# 32-16_adapter2.net
KiCad netlist of a schematic drawn in EAGLE
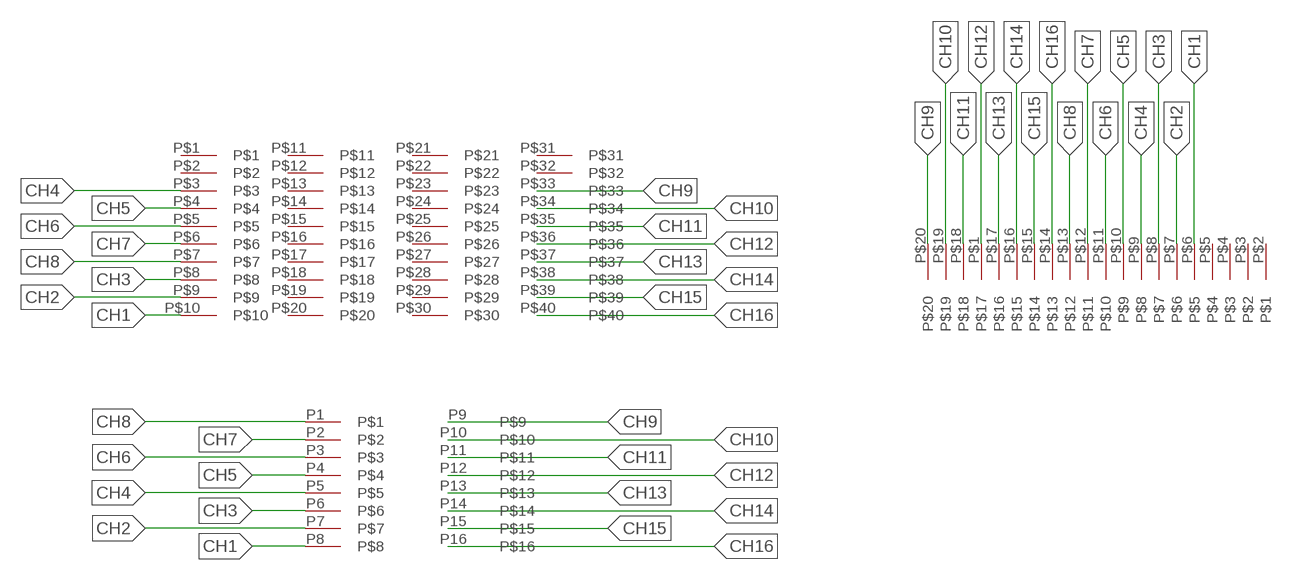
[diagram p0: schematic, sheet 1]

(export (version "E")
  (design (tool "Eeschema 10.0.6"))
  (components
    (comp (ref "U$1")
      (value "16_PAD")
      (footprint "eagle-import:16_PAD")
      (libsource (lib "eagle-import") (part "16_PAD"))
    )
    (comp (ref "U$2")
      (value "DIL-16CHN")
      (footprint "eagle-import:DIL-16CHN")
      (libsource (lib "eagle-import") (part "DIL-16CHN"))
    )
    (comp (ref "U$3")
      (value "MOLC-SAMTEC-32")
      (footprint "eagle-import:MOLC-SAMTEC-32")
      (libsource (lib "eagle-import") (part "MOLC-SAMTEC-32"))
    )
  )
  (nets
    (net (code "1") (name "CH1") (class "Default")
      (node (ref "U$1") (pin "P$6") (pinfunction "P$5_P$6") (pintype "bidirectional"))
      (node (ref "U$2") (pin "P8") (pinfunction "P$8_P8") (pintype "bidirectional"))
      (node (ref "U$3") (pin "P$10") (pinfunction "P$10_P$10") (pintype "bidirectional"))
    )
    (net (code "2") (name "CH2") (class "Default")
      (node (ref "U$1") (pin "P$7") (pinfunction "P$6_P$7") (pintype "bidirectional"))
      (node (ref "U$2") (pin "P7") (pinfunction "P$7_P7") (pintype "bidirectional"))
      (node (ref "U$3") (pin "P$9") (pinfunction "P$9_P$9") (pintype "bidirectional"))
    )
    (net (code "3") (name "CH3") (class "Default")
      (node (ref "U$1") (pin "P$8") (pinfunction "P$7_P$8") (pintype "bidirectional"))
      (node (ref "U$2") (pin "P6") (pinfunction "P$6_P6") (pintype "bidirectional"))
      (node (ref "U$3") (pin "P$8") (pinfunction "P$8_P$8") (pintype "bidirectional"))
    )
    (net (code "4") (name "CH4") (class "Default")
      (node (ref "U$1") (pin "P$9") (pinfunction "P$8_P$9") (pintype "bidirectional"))
      (node (ref "U$2") (pin "P5") (pinfunction "P$5_P5") (pintype "bidirectional"))
      (node (ref "U$3") (pin "P$3") (pinfunction "P$3_P$3") (pintype "bidirectional"))
    )
    (net (code "5") (name "CH5") (class "Default")
      (node (ref "U$1") (pin "P$10") (pinfunction "P$9_P$10") (pintype "bidirectional"))
      (node (ref "U$2") (pin "P4") (pinfunction "P$4_P4") (pintype "bidirectional"))
      (node (ref "U$3") (pin "P$4") (pinfunction "P$4_P$4") (pintype "bidirectional"))
    )
    (net (code "6") (name "CH6") (class "Default")
      (node (ref "U$1") (pin "P$11") (pinfunction "P$10_P$11") (pintype "bidirectional"))
      (node (ref "U$2") (pin "P3") (pinfunction "P$3_P3") (pintype "bidirectional"))
      (node (ref "U$3") (pin "P$5") (pinfunction "P$5_P$5") (pintype "bidirectional"))
    )
    (net (code "7") (name "CH7") (class "Default")
      (node (ref "U$1") (pin "P$12") (pinfunction "P$11_P$12") (pintype "bidirectional"))
      (node (ref "U$2") (pin "P2") (pinfunction "P$2_P2") (pintype "bidirectional"))
      (node (ref "U$3") (pin "P$6") (pinfunction "P$6_P$6") (pintype "bidirectional"))
    )
    (net (code "8") (name "CH8") (class "Default")
      (node (ref "U$1") (pin "P$13") (pinfunction "P$12_P$13") (pintype "bidirectional"))
      (node (ref "U$2") (pin "P1") (pinfunction "P$1_P1") (pintype "bidirectional"))
      (node (ref "U$3") (pin "P$7") (pinfunction "P$7_P$7") (pintype "bidirectional"))
    )
    (net (code "9") (name "CH9") (class "Default")
      (node (ref "U$1") (pin "P$20") (pinfunction "P$20_P$20") (pintype "bidirectional"))
      (node (ref "U$2") (pin "P9") (pinfunction "P$9_P9") (pintype "bidirectional"))
      (node (ref "U$3") (pin "P$33") (pinfunction "P$33_P$33") (pintype "bidirectional"))
    )
    (net (code "10") (name "CH10") (class "Default")
      (node (ref "U$1") (pin "P$19") (pinfunction "P$19_P$19") (pintype "bidirectional"))
      (node (ref "U$2") (pin "P10") (pinfunction "P$10_P10") (pintype "bidirectional"))
      (node (ref "U$3") (pin "P$34") (pinfunction "P$34_P$34") (pintype "bidirectional"))
    )
    (net (code "11") (name "CH11") (class "Default")
      (node (ref "U$1") (pin "P$18") (pinfunction "P$18_P$18") (pintype "bidirectional"))
      (node (ref "U$2") (pin "P11") (pinfunction "P$11_P11") (pintype "bidirectional"))
      (node (ref "U$3") (pin "P$35") (pinfunction "P$35_P$35") (pintype "bidirectional"))
    )
    (net (code "12") (name "CH12") (class "Default")
      (node (ref "U$1") (pin "P$1") (pinfunction "P$17_P$1") (pintype "bidirectional"))
      (node (ref "U$2") (pin "P12") (pinfunction "P$12_P12") (pintype "bidirectional"))
      (node (ref "U$3") (pin "P$36") (pinfunction "P$36_P$36") (pintype "bidirectional"))
    )
    (net (code "13") (name "CH13") (class "Default")
      (node (ref "U$1") (pin "P$17") (pinfunction "P$16_P$17") (pintype "bidirectional"))
      (node (ref "U$2") (pin "P13") (pinfunction "P$13_P13") (pintype "bidirectional"))
      (node (ref "U$3") (pin "P$37") (pinfunction "P$37_P$37") (pintype "bidirectional"))
    )
    (net (code "14") (name "CH14") (class "Default")
      (node (ref "U$1") (pin "P$16") (pinfunction "P$15_P$16") (pintype "bidirectional"))
      (node (ref "U$2") (pin "P14") (pinfunction "P$14_P14") (pintype "bidirectional"))
      (node (ref "U$3") (pin "P$38") (pinfunction "P$38_P$38") (pintype "bidirectional"))
    )
    (net (code "15") (name "CH15") (class "Default")
      (node (ref "U$1") (pin "P$15") (pinfunction "P$14_P$15") (pintype "bidirectional"))
      (node (ref "U$2") (pin "P15") (pinfunction "P$15_P15") (pintype "bidirectional"))
      (node (ref "U$3") (pin "P$39") (pinfunction "P$39_P$39") (pintype "bidirectional"))
    )
    (net (code "16") (name "CH16") (class "Default")
      (node (ref "U$1") (pin "P$14") (pinfunction "P$13_P$14") (pintype "bidirectional"))
      (node (ref "U$2") (pin "P16") (pinfunction "P$16_P16") (pintype "bidirectional"))
      (node (ref "U$3") (pin "P$40") (pinfunction "P$40_P$40") (pintype "bidirectional"))
    )
    (net (code "17") (name "unconnected-(U$1-P$1-PadP$2)") (class "Default")
      (node (ref "U$1") (pin "P$2") (pinfunction "P$1_P$2") (pintype "bidirectional"))
    )
    (net (code "18") (name "unconnected-(U$1-P$2-PadP$3)") (class "Default")
      (node (ref "U$1") (pin "P$3") (pinfunction "P$2_P$3") (pintype "bidirectional"))
    )
    (net (code "19") (name "unconnected-(U$1-P$3-PadP$4)") (class "Default")
      (node (ref "U$1") (pin "P$4") (pinfunction "P$3_P$4") (pintype "bidirectional"))
    )
    (net (code "20") (name "unconnected-(U$1-P$4-PadP$5)") (class "Default")
      (node (ref "U$1") (pin "P$5") (pinfunction "P$4_P$5") (pintype "bidirectional"))
    )
    (net (code "21") (name "unconnected-(U$3-PadP$1)") (class "Default")
      (node (ref "U$3") (pin "P$1") (pinfunction "P$1_P$1") (pintype "bidirectional"))
    )
    (net (code "22") (name "unconnected-(U$3-PadP$2)") (class "Default")
      (node (ref "U$3") (pin "P$2") (pinfunction "P$2_P$2") (pintype "bidirectional"))
    )
    (net (code "23") (name "unconnected-(U$3-PadP$11)") (class "Default")
      (node (ref "U$3") (pin "P$11") (pinfunction "P$11_P$11") (pintype "bidirectional"))
    )
    (net (code "24") (name "unconnected-(U$3-PadP$12)") (class "Default")
      (node (ref "U$3") (pin "P$12") (pinfunction "P$12_P$12") (pintype "bidirectional"))
    )
    (net (code "25") (name "unconnected-(U$3-PadP$13)") (class "Default")
      (node (ref "U$3") (pin "P$13") (pinfunction "P$13_P$13") (pintype "bidirectional"))
    )
    (net (code "26") (name "unconnected-(U$3-PadP$14)") (class "Default")
      (node (ref "U$3") (pin "P$14") (pinfunction "P$14_P$14") (pintype "bidirectional"))
    )
    (net (code "27") (name "unconnected-(U$3-PadP$15)") (class "Default")
      (node (ref "U$3") (pin "P$15") (pinfunction "P$15_P$15") (pintype "bidirectional"))
    )
    (net (code "28") (name "unconnected-(U$3-PadP$16)") (class "Default")
      (node (ref "U$3") (pin "P$16") (pinfunction "P$16_P$16") (pintype "bidirectional"))
    )
    (net (code "29") (name "unconnected-(U$3-PadP$17)") (class "Default")
      (node (ref "U$3") (pin "P$17") (pinfunction "P$17_P$17") (pintype "bidirectional"))
    )
    (net (code "30") (name "unconnected-(U$3-PadP$18)") (class "Default")
      (node (ref "U$3") (pin "P$18") (pinfunction "P$18_P$18") (pintype "bidirectional"))
    )
    (net (code "31") (name "unconnected-(U$3-PadP$19)") (class "Default")
      (node (ref "U$3") (pin "P$19") (pinfunction "P$19_P$19") (pintype "bidirectional"))
    )
    (net (code "32") (name "unconnected-(U$3-PadP$20)") (class "Default")
      (node (ref "U$3") (pin "P$20") (pinfunction "P$20_P$20") (pintype "bidirectional"))
    )
    (net (code "33") (name "unconnected-(U$3-PadP$21)") (class "Default")
      (node (ref "U$3") (pin "P$21") (pinfunction "P$21_P$21") (pintype "bidirectional"))
    )
    (net (code "34") (name "unconnected-(U$3-PadP$22)") (class "Default")
      (node (ref "U$3") (pin "P$22") (pinfunction "P$22_P$22") (pintype "bidirectional"))
    )
    (net (code "35") (name "unconnected-(U$3-PadP$23)") (class "Default")
      (node (ref "U$3") (pin "P$23") (pinfunction "P$23_P$23") (pintype "bidirectional"))
    )
    (net (code "36") (name "unconnected-(U$3-PadP$24)") (class "Default")
      (node (ref "U$3") (pin "P$24") (pinfunction "P$24_P$24") (pintype "bidirectional"))
    )
    (net (code "37") (name "unconnected-(U$3-PadP$25)") (class "Default")
      (node (ref "U$3") (pin "P$25") (pinfunction "P$25_P$25") (pintype "bidirectional"))
    )
    (net (code "38") (name "unconnected-(U$3-PadP$26)") (class "Default")
      (node (ref "U$3") (pin "P$26") (pinfunction "P$26_P$26") (pintype "bidirectional"))
    )
    (net (code "39") (name "unconnected-(U$3-PadP$27)") (class "Default")
      (node (ref "U$3") (pin "P$27") (pinfunction "P$27_P$27") (pintype "bidirectional"))
    )
    (net (code "40") (name "unconnected-(U$3-PadP$28)") (class "Default")
      (node (ref "U$3") (pin "P$28") (pinfunction "P$28_P$28") (pintype "bidirectional"))
    )
    (net (code "41") (name "unconnected-(U$3-PadP$29)") (class "Default")
      (node (ref "U$3") (pin "P$29") (pinfunction "P$29_P$29") (pintype "bidirectional"))
    )
    (net (code "42") (name "unconnected-(U$3-PadP$30)") (class "Default")
      (node (ref "U$3") (pin "P$30") (pinfunction "P$30_P$30") (pintype "bidirectional"))
    )
    (net (code "43") (name "unconnected-(U$3-PadP$31)") (class "Default")
      (node (ref "U$3") (pin "P$31") (pinfunction "P$31_P$31") (pintype "bidirectional"))
    )
    (net (code "44") (name "unconnected-(U$3-PadP$32)") (class "Default")
      (node (ref "U$3") (pin "P$32") (pinfunction "P$32_P$32") (pintype "bidirectional"))
    )
  )
)
